# AirQ.net
KiCad netlist of a schematic drawn in Altium Designer
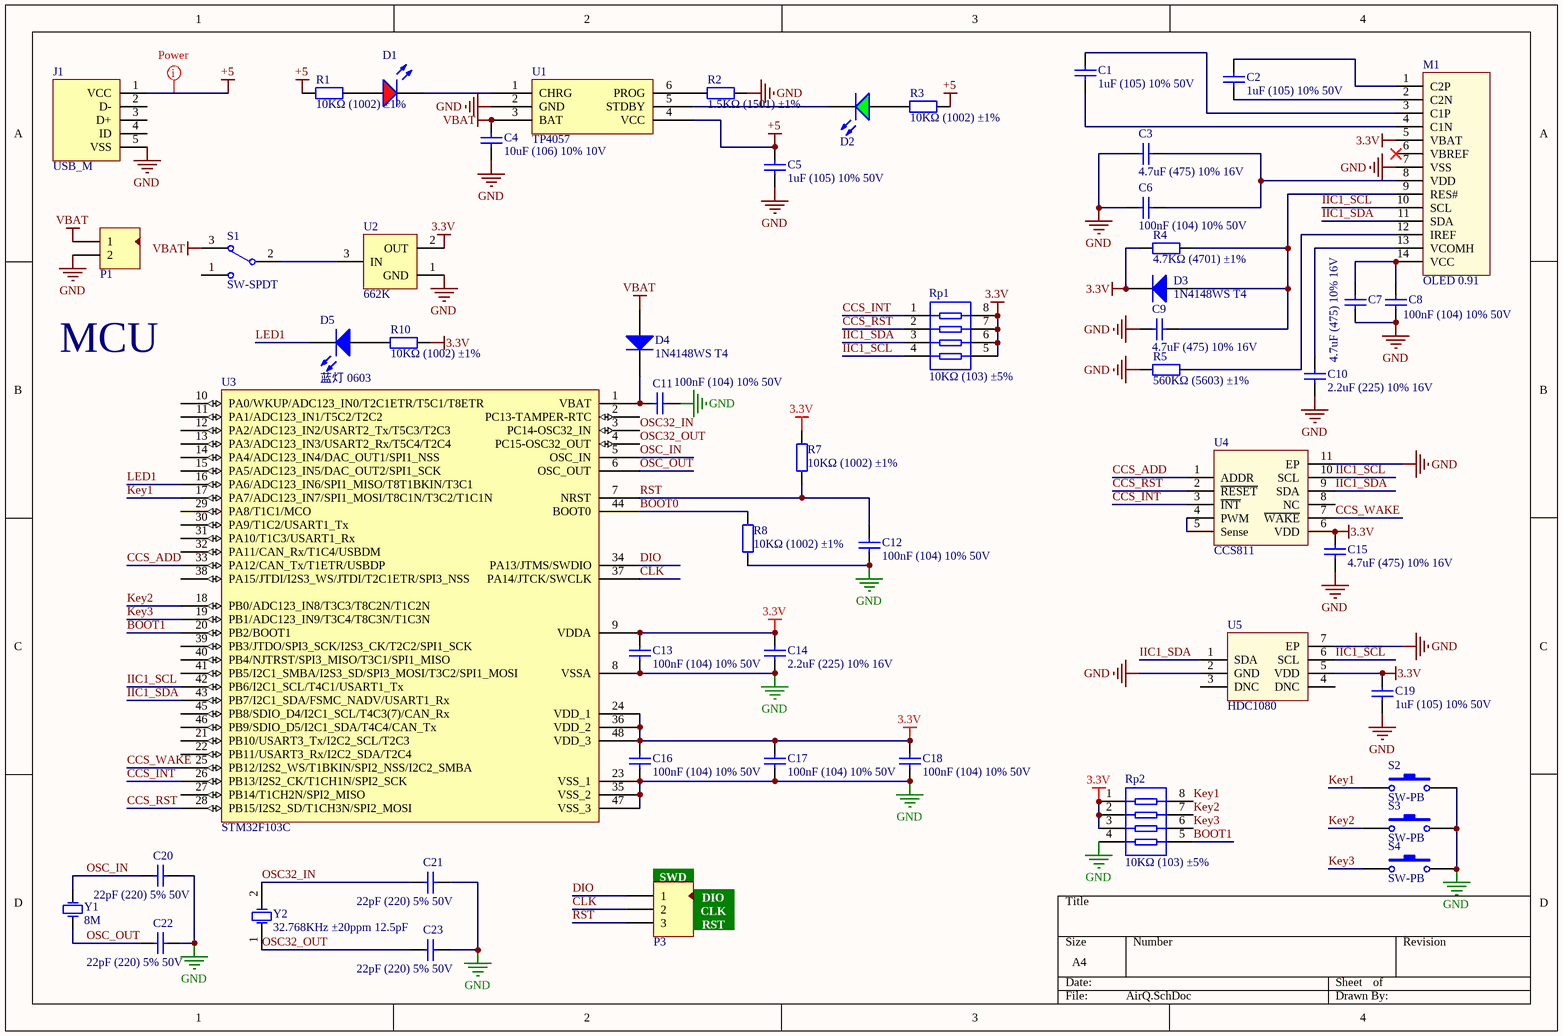
[diagram p0: AirQ.SchDoc]

(export (version "E")
  (design (tool "Eeschema 10.0.6"))
  (components
    (comp (ref "C1")
      (value "1uF (105) 10% 50V")
      (footprint "0603_C")
      (description "贴片电容")
      (libsource (lib "Miscellaneous Devices LC") (part "0603 1uF (105) 10% 50V"))
    )
    (comp (ref "C2")
      (value "1uF (105) 10% 50V")
      (footprint "0603_C")
      (description "贴片电容")
      (libsource (lib "Miscellaneous Devices LC") (part "0603 1uF (105) 10% 50V"))
    )
    (comp (ref "C3")
      (value "4.7uF (475) 10% 16V")
      (footprint "0603_C")
      (description "贴片电容")
      (libsource (lib "Miscellaneous Devices LC") (part "0603 4.7uF (475) 10% 16V"))
    )
    (comp (ref "C4")
      (value "10uF (106) 10% 10V")
      (footprint "0603_C")
      (description "贴片电容")
      (libsource (lib "Miscellaneous Devices LC") (part "0603 10uF (106) 10% 10V"))
    )
    (comp (ref "C5")
      (value "1uF (105) 10% 50V")
      (footprint "0603_C")
      (description "贴片电容")
      (libsource (lib "Miscellaneous Devices LC") (part "0603 1uF (105) 10% 50V"))
    )
    (comp (ref "C6")
      (value "100nF (104) 10% 50V")
      (footprint "0603_C")
      (description "贴片电容")
      (libsource (lib "Miscellaneous Devices LC") (part "0603 100nF (104) 10% 50V"))
    )
    (comp (ref "C7")
      (value "4.7uF (475) 10% 16V")
      (footprint "0603_C")
      (description "贴片电容")
      (libsource (lib "Miscellaneous Devices LC") (part "0603 4.7uF (475) 10% 16V"))
    )
    (comp (ref "C8")
      (value "100nF (104) 10% 50V")
      (footprint "0603_C")
      (description "贴片电容")
      (libsource (lib "Miscellaneous Devices LC") (part "0603 100nF (104) 10% 50V"))
    )
    (comp (ref "C9")
      (value "4.7uF (475) 10% 16V")
      (footprint "0603_C")
      (description "贴片电容")
      (libsource (lib "Miscellaneous Devices LC") (part "0603 4.7uF (475) 10% 16V"))
    )
    (comp (ref "C10")
      (value "2.2uF (225) 10% 16V")
      (footprint "0603_C")
      (description "贴片电容")
      (libsource (lib "Miscellaneous Devices LC") (part "0603 2.2uF (225) 10% 16V"))
    )
    (comp (ref "C11")
      (value "100nF (104) 10% 50V")
      (footprint "0603_C")
      (description "贴片电容")
      (libsource (lib "Miscellaneous Devices LC") (part "0603 100nF (104) 10% 50V"))
    )
    (comp (ref "C12")
      (value "100nF (104) 10% 50V")
      (footprint "0603_C")
      (description "贴片电容")
      (libsource (lib "Miscellaneous Devices LC") (part "0603 100nF (104) 10% 50V"))
    )
    (comp (ref "C13")
      (value "100nF (104) 10% 50V")
      (footprint "0603_C")
      (description "贴片电容")
      (libsource (lib "Miscellaneous Devices LC") (part "0603 100nF (104) 10% 50V"))
    )
    (comp (ref "C14")
      (value "2.2uF (225) 10% 16V")
      (footprint "0603_C")
      (description "贴片电容")
      (libsource (lib "Miscellaneous Devices LC") (part "0603 2.2uF (225) 10% 16V"))
    )
    (comp (ref "C15")
      (value "4.7uF (475) 10% 16V")
      (footprint "0603_C")
      (description "贴片电容")
      (libsource (lib "Miscellaneous Devices LC") (part "0603 4.7uF (475) 10% 16V"))
    )
    (comp (ref "C16")
      (value "100nF (104) 10% 50V")
      (footprint "0603_C")
      (description "贴片电容")
      (libsource (lib "Miscellaneous Devices LC") (part "0603 100nF (104) 10% 50V"))
    )
    (comp (ref "C17")
      (value "100nF (104) 10% 50V")
      (footprint "0603_C")
      (description "贴片电容")
      (libsource (lib "Miscellaneous Devices LC") (part "0603 100nF (104) 10% 50V"))
    )
    (comp (ref "C18")
      (value "100nF (104) 10% 50V")
      (footprint "0603_C")
      (description "贴片电容")
      (libsource (lib "Miscellaneous Devices LC") (part "0603 100nF (104) 10% 50V"))
    )
    (comp (ref "C19")
      (value "1uF (105) 10% 50V")
      (footprint "0603_C")
      (description "贴片电容")
      (libsource (lib "Miscellaneous Devices LC") (part "0603 1uF (105) 10% 50V"))
    )
    (comp (ref "C20")
      (value "22pF (220) 5% 50V")
      (footprint "0603_C")
      (description "贴片电容")
      (libsource (lib "Miscellaneous Devices LC") (part "0603 22pF (220) 5% 50V"))
    )
    (comp (ref "C21")
      (value "22pF (220) 5% 50V")
      (footprint "0603_C")
      (description "贴片电容")
      (libsource (lib "Miscellaneous Devices LC") (part "0603 22pF (220) 5% 50V"))
    )
    (comp (ref "C22")
      (value "22pF (220) 5% 50V")
      (footprint "0603_C")
      (description "贴片电容")
      (libsource (lib "Miscellaneous Devices LC") (part "0603 22pF (220) 5% 50V"))
    )
    (comp (ref "C23")
      (value "22pF (220) 5% 50V")
      (footprint "0603_C")
      (description "贴片电容")
      (libsource (lib "Miscellaneous Devices LC") (part "0603 22pF (220) 5% 50V"))
    )
    (comp (ref "D1")
      (value "红灯 0603")
      (footprint "0603_LED_S1")
      (description "发光二极管")
      (libsource (lib "Miscellaneous Devices LC") (part "0603 红灯"))
    )
    (comp (ref "D2")
      (value "绿灯 0603")
      (footprint "0603_LED_S1")
      (description "发光二极管")
      (libsource (lib "Miscellaneous Devices LC") (part "0603 绿灯"))
    )
    (comp (ref "D3")
      (value "1N4148WS T4")
      (footprint "SOD-323")
      (description "二极管")
      (libsource (lib "Miscellaneous Devices LC") (part "SOD-323 1N4148WS T4"))
    )
    (comp (ref "D4")
      (value "1N4148WS T4")
      (footprint "SOD-323")
      (description "二极管")
      (libsource (lib "Miscellaneous Devices LC") (part "SOD-323 1N4148WS T4"))
    )
    (comp (ref "D5")
      (value "蓝灯 0603")
      (footprint "0603_LED_S1")
      (description "发光二极管")
      (libsource (lib "Miscellaneous Devices LC") (part "0603 蓝灯"))
    )
    (comp (ref "J1")
      (value "USB_M")
      (footprint "USB-MICRO-A01SB141B1-261")
      (description "Micro/Mini USB")
      (libsource (lib "interface") (part "USB_M"))
    )
    (comp (ref "M1")
      (value "OLED 0.91")
      (footprint "OLED 0.91 BOTTOM")
      (description "0.91寸OLED裸屏")
      (libsource (lib "function module") (part "OLED-0.91"))
    )
    (comp (ref "P1")
      (value "Header 2")
      (footprint "HDR2X1-2.54")
      (description "接插件")
      (fields (field (name "PUBLISHER") "Altium Limited"))
      (libsource (lib "interface") (part "Header 2"))
    )
    (comp (ref "P3")
      (value "Header 3")
      (footprint "HDR3X1-2.54")
      (description "接插件")
      (fields (field (name "PUBLISHER") "Altium Limited"))
      (libsource (lib "interface") (part "Header 3"))
    )
    (comp (ref "R1")
      (value "10KΩ (1002) ±1%")
      (footprint "0603_R")
      (description "贴片电阻")
      (libsource (lib "Miscellaneous Devices LC") (part "0603 10KΩ (1002) 1%"))
    )
    (comp (ref "R2")
      (value "1.5KΩ (1501) ±1%")
      (footprint "0603_R")
      (description "贴片电阻")
      (libsource (lib "Miscellaneous Devices LC") (part "0603 1.5KΩ (1501) 1%"))
    )
    (comp (ref "R3")
      (value "10KΩ (1002) ±1%")
      (footprint "0603_R")
      (description "贴片电阻")
      (libsource (lib "") (part "0603 10KΩ (1002) 1%_1"))
    )
    (comp (ref "R4")
      (value "4.7KΩ (4701) ±1%")
      (footprint "0603_R")
      (description "贴片电阻")
      (libsource (lib "Miscellaneous Devices LC") (part "0603 4.7KΩ (4701) 1%"))
    )
    (comp (ref "R5")
      (value "560KΩ (5603) ±1%")
      (footprint "0603_R")
      (description "贴片电阻")
      (libsource (lib "Miscellaneous Devices LC") (part "0603 560KΩ (5603) 1%"))
    )
    (comp (ref "R7")
      (value "10KΩ (1002) ±1%")
      (footprint "0603_R")
      (description "贴片电阻")
      (libsource (lib "") (part "0603 10KΩ (1002) 1%_2"))
    )
    (comp (ref "R8")
      (value "10KΩ (1002) ±1%")
      (footprint "0603_R")
      (description "贴片电阻")
      (libsource (lib "") (part "0603 10KΩ (1002) 1%_2"))
    )
    (comp (ref "R10")
      (value "10KΩ (1002) ±1%")
      (footprint "0603_R")
      (description "贴片电阻")
      (libsource (lib "") (part "0603 10KΩ (1002) 1%_1"))
    )
    (comp (ref "Rp1")
      (value "10KΩ (103) ±5%")
      (footprint "0603_Rx4")
      (description "贴片排阻")
      (libsource (lib "Miscellaneous Devices LC") (part "0603*4  10KΩ (103) 5%"))
    )
    (comp (ref "Rp2")
      (value "10KΩ (103) ±5%")
      (footprint "0603_Rx4")
      (description "贴片排阻")
      (libsource (lib "Miscellaneous Devices LC") (part "0603*4  10KΩ (103) 5%"))
    )
    (comp (ref "S1")
      (value "SW-SPDT")
      (footprint "SWITCH_SMT1")
      (description "开关")
      (fields (field (name "PUBLISHER") "Altium Limited"))
      (libsource (lib "Fszhang") (part "SW-SPDT"))
    )
    (comp (ref "S2")
      (value "SW-PB")
      (footprint "SW_PB2_A1")
      (description "微动开关")
      (fields (field (name "PUBLISHER") "Altium Limited"))
      (libsource (lib "fszhang") (part "SW-PB"))
    )
    (comp (ref "S3")
      (value "SW-PB")
      (footprint "SW_PB2_A1")
      (description "微动开关")
      (fields (field (name "PUBLISHER") "Altium Limited"))
      (libsource (lib "fszhang") (part "SW-PB"))
    )
    (comp (ref "S4")
      (value "SW-PB")
      (footprint "SW_PB2_A1")
      (description "微动开关")
      (fields (field (name "PUBLISHER") "Altium Limited"))
      (libsource (lib "fszhang") (part "SW-PB"))
    )
    (comp (ref "U1")
      (value "TP4057")
      (footprint "SOT-23-6")
      (description "电池电源管理")
      (libsource (lib "Miscellaneous Devices LC") (part "TP4057_[C12044]"))
    )
    (comp (ref "U2")
      (value "662K")
      (footprint "SOT23-3")
      (description "3.3V稳压三极管 662K")
      (libsource (lib "Fszhang") (part "XC6206P332MR"))
    )
    (comp (ref "U3")
      (value "STM32F103C")
      (footprint "LQFP-48")
      (description "STM32单片机48引脚")
      (libsource (lib "Fszhang") (part "STM32F103C"))
    )
    (comp (ref "U4")
      (value "CCS811")
      (footprint "CCS811")
      (description "空气质量检测")
      (libsource (lib "Sensor") (part "CCS811"))
    )
    (comp (ref "U5")
      (value "HDC1080")
      (footprint "HDC1080")
      (description "温湿度传感器")
      (libsource (lib "Sensor") (part "HDC1080"))
    )
    (comp (ref "Y1")
      (value "8M")
      (footprint "5032 - 2Pin")
      (description "晶振")
      (fields (field (name "Comment") "XTAL") (field (name "PUBLISHER") "Altium Limited"))
      (libsource (lib "fszhang") (part "XTAL"))
    )
    (comp (ref "Y2")
      (value "32.768KHz ±20ppm 12.5pF")
      (footprint "SMD-3215_2P FC - 135")
      (description "贴片晶振")
      (libsource (lib "Miscellaneous Devices LC") (part "SMD-3215_2P 32.768KHz 20ppm 12.5pF"))
    )
  )
  (nets
    (net (code "1") (name "+5") (class "Default")
      (node (ref "C5") (pin "2") (pinfunction "2_2") (pintype "passive"))
      (node (ref "J1") (pin "1") (pinfunction "VCC_1") (pintype "power_in"))
      (node (ref "R1") (pin "1") (pinfunction "1_1") (pintype "passive"))
      (node (ref "R3") (pin "1") (pinfunction "1_1") (pintype "passive"))
      (node (ref "U1") (pin "4") (pinfunction "VCC_4") (pintype "passive"))
    )
    (net (code "2") (name "/BOOT0") (class "Default")
      (node (ref "R8") (pin "2") (pinfunction "2_2") (pintype "passive"))
      (node (ref "U3") (pin "44") (pinfunction "BOOT0_44") (pintype "passive"))
    )
    (net (code "3") (name "/BOOT1") (class "Default")
      (node (ref "Rp2") (pin "5") (pinfunction "5_5") (pintype "passive"))
      (node (ref "U3") (pin "20") (pinfunction "PB2/BOOT1_20") (pintype "bidirectional"))
    )
    (net (code "4") (name "/CCS_ADD") (class "Default")
      (node (ref "U3") (pin "33") (pinfunction "PA12/CAN_Tx/T1ETR/USBDP_33") (pintype "bidirectional"))
      (node (ref "U4") (pin "1") (pinfunction "ADDR_1") (pintype "passive"))
    )
    (net (code "5") (name "/CCS_INT") (class "Default")
      (node (ref "Rp1") (pin "1") (pinfunction "1_1") (pintype "passive"))
      (node (ref "U3") (pin "26") (pinfunction "PB13/I2S2_CK/T1CH1N/SPI2_SCK_26") (pintype "bidirectional"))
      (node (ref "U4") (pin "3") (pinfunction "~{INT}_3") (pintype "passive"))
    )
    (net (code "6") (name "/CCS_RST") (class "Default")
      (node (ref "Rp1") (pin "2") (pinfunction "2_2") (pintype "passive"))
      (node (ref "U3") (pin "28") (pinfunction "PB15/I2S2_SD/T1CH3N/SPI2_MOSI_28") (pintype "bidirectional"))
      (node (ref "U4") (pin "2") (pinfunction "~{RESET}_2") (pintype "passive"))
    )
    (net (code "7") (name "/CCS_WAKE") (class "Default")
      (node (ref "U3") (pin "25") (pinfunction "PB12/I2S2_WS/T1BKIN/SPI2_NSS/I2C2_SMBA_25") (pintype "bidirectional"))
      (node (ref "U4") (pin "7") (pinfunction "~{WAKE}_7") (pintype "passive"))
    )
    (net (code "8") (name "/CLK") (class "Default")
      (node (ref "P3") (pin "2") (pinfunction "2_2") (pintype "passive"))
      (node (ref "U3") (pin "37") (pinfunction "PA14/JTCK/SWCLK_37") (pintype "passive"))
    )
    (net (code "9") (name "/DIO") (class "Default")
      (node (ref "P3") (pin "1") (pinfunction "1_1") (pintype "passive"))
      (node (ref "U3") (pin "34") (pinfunction "PA13/JTMS/SWDIO_34") (pintype "passive"))
    )
    (net (code "10") (name "/IIC1_SCL") (class "Default")
      (node (ref "M1") (pin "10") (pinfunction "SCL_10") (pintype "passive"))
      (node (ref "Rp1") (pin "4") (pinfunction "4_4") (pintype "passive"))
      (node (ref "U3") (pin "42") (pinfunction "PB6/I2C1_SCL/T4C1/USART1_Tx_42") (pintype "bidirectional"))
      (node (ref "U4") (pin "10") (pinfunction "SCL_10") (pintype "passive"))
      (node (ref "U5") (pin "6") (pinfunction "SCL_6") (pintype "passive"))
    )
    (net (code "11") (name "/IIC1_SDA") (class "Default")
      (node (ref "M1") (pin "11") (pinfunction "SDA_11") (pintype "passive"))
      (node (ref "Rp1") (pin "3") (pinfunction "3_3") (pintype "passive"))
      (node (ref "U3") (pin "43") (pinfunction "PB7/I2C1_SDA/FSMC_NADV/USART1_Rx_43") (pintype "bidirectional"))
      (node (ref "U4") (pin "9") (pinfunction "SDA_9") (pintype "passive"))
      (node (ref "U5") (pin "1") (pinfunction "SDA_1") (pintype "passive"))
    )
    (net (code "12") (name "/Key1") (class "Default")
      (node (ref "Rp2") (pin "8") (pinfunction "8_8") (pintype "passive"))
      (node (ref "S2") (pin "1") (pinfunction "1_1") (pintype "passive"))
      (node (ref "U3") (pin "17") (pinfunction "PA7/ADC123_IN7/SPI1_MOSI/T8C1N/T3C2/T1C1N_17") (pintype "bidirectional"))
    )
    (net (code "13") (name "/Key2") (class "Default")
      (node (ref "Rp2") (pin "7") (pinfunction "7_7") (pintype "passive"))
      (node (ref "S3") (pin "1") (pinfunction "1_1") (pintype "passive"))
      (node (ref "U3") (pin "18") (pinfunction "PB0/ADC123_IN8/T3C3/T8C2N/T1C2N_18") (pintype "bidirectional"))
    )
    (net (code "14") (name "/Key3") (class "Default")
      (node (ref "Rp2") (pin "6") (pinfunction "6_6") (pintype "passive"))
      (node (ref "S4") (pin "1") (pinfunction "1_1") (pintype "passive"))
      (node (ref "U3") (pin "19") (pinfunction "PB1/ADC123_IN9/T3C4/T8C3N/T1C3N_19") (pintype "bidirectional"))
    )
    (net (code "15") (name "/LED1") (class "Default")
      (node (ref "D5") (pin "K") (pinfunction "K_K") (pintype "passive"))
      (node (ref "U3") (pin "16") (pinfunction "PA6/ADC123_IN6/SPI1_MISO/T8T1BKIN/T3C1_16") (pintype "bidirectional"))
    )
    (net (code "16") (name "/OSC32_IN") (class "Default")
      (node (ref "C21") (pin "1") (pinfunction "1_1") (pintype "passive"))
      (node (ref "U3") (pin "3") (pinfunction "PC14-OSC32_IN_3") (pintype "bidirectional"))
      (node (ref "Y2") (pin "2") (pinfunction "OSC2_2") (pintype "passive"))
    )
    (net (code "17") (name "/OSC32_OUT") (class "Default")
      (node (ref "C23") (pin "1") (pinfunction "1_1") (pintype "passive"))
      (node (ref "U3") (pin "4") (pinfunction "PC15-OSC32_OUT_4") (pintype "bidirectional"))
      (node (ref "Y2") (pin "1") (pinfunction "OSC1_1") (pintype "passive"))
    )
    (net (code "18") (name "/OSC_IN") (class "Default")
      (node (ref "C20") (pin "1") (pinfunction "1_1") (pintype "passive"))
      (node (ref "U3") (pin "5") (pinfunction "OSC_IN_5") (pintype "passive"))
      (node (ref "Y1") (pin "2") (pinfunction "OSC2_2") (pintype "passive"))
    )
    (net (code "19") (name "/OSC_OUT") (class "Default")
      (node (ref "C22") (pin "1") (pinfunction "1_1") (pintype "passive"))
      (node (ref "U3") (pin "6") (pinfunction "OSC_OUT_6") (pintype "passive"))
      (node (ref "Y1") (pin "1") (pinfunction "OSC1_1") (pintype "passive"))
    )
    (net (code "20") (name "/RST") (class "Default")
      (node (ref "C12") (pin "2") (pinfunction "2_2") (pintype "passive"))
      (node (ref "P3") (pin "3") (pinfunction "3_3") (pintype "passive"))
      (node (ref "R7") (pin "1") (pinfunction "1_1") (pintype "passive"))
      (node (ref "U3") (pin "7") (pinfunction "NRST_7") (pintype "passive"))
    )
    (net (code "21") (name "3.3V") (class "Default")
      (node (ref "C13") (pin "2") (pinfunction "2_2") (pintype "passive"))
      (node (ref "C14") (pin "2") (pinfunction "2_2") (pintype "passive"))
      (node (ref "C15") (pin "2") (pinfunction "2_2") (pintype "passive"))
      (node (ref "C16") (pin "2") (pinfunction "2_2") (pintype "passive"))
      (node (ref "C17") (pin "2") (pinfunction "2_2") (pintype "passive"))
      (node (ref "C18") (pin "2") (pinfunction "2_2") (pintype "passive"))
      (node (ref "C19") (pin "2") (pinfunction "2_2") (pintype "passive"))
      (node (ref "D3") (pin "2") (pinfunction "K_2") (pintype "passive"))
      (node (ref "M1") (pin "5") (pinfunction "VBAT_5") (pintype "passive"))
      (node (ref "R10") (pin "1") (pinfunction "1_1") (pintype "passive"))
      (node (ref "R4") (pin "2") (pinfunction "2_2") (pintype "passive"))
      (node (ref "R7") (pin "2") (pinfunction "2_2") (pintype "passive"))
      (node (ref "Rp1") (pin "5") (pinfunction "5_5") (pintype "passive"))
      (node (ref "Rp1") (pin "6") (pinfunction "6_6") (pintype "passive"))
      (node (ref "Rp1") (pin "7") (pinfunction "7_7") (pintype "passive"))
      (node (ref "Rp1") (pin "8") (pinfunction "8_8") (pintype "passive"))
      (node (ref "Rp2") (pin "1") (pinfunction "1_1") (pintype "passive"))
      (node (ref "Rp2") (pin "2") (pinfunction "2_2") (pintype "passive"))
      (node (ref "Rp2") (pin "3") (pinfunction "3_3") (pintype "passive"))
      (node (ref "U2") (pin "2") (pinfunction "OUT_2") (pintype "passive"))
      (node (ref "U3") (pin "24") (pinfunction "VDD_1_24") (pintype "passive"))
      (node (ref "U3") (pin "36") (pinfunction "VDD_2_36") (pintype "passive"))
      (node (ref "U3") (pin "48") (pinfunction "VDD_3_48") (pintype "passive"))
      (node (ref "U3") (pin "9") (pinfunction "VDDA_9") (pintype "passive"))
      (node (ref "U4") (pin "6") (pinfunction "VDD_6") (pintype "passive"))
      (node (ref "U5") (pin "5") (pinfunction "VDD_5") (pintype "passive"))
    )
    (net (code "22") (name "GND") (class "Default")
      (node (ref "C10") (pin "1") (pinfunction "1_1") (pintype "passive"))
      (node (ref "C11") (pin "1") (pinfunction "1_1") (pintype "passive"))
      (node (ref "C12") (pin "1") (pinfunction "1_1") (pintype "passive"))
      (node (ref "C13") (pin "1") (pinfunction "1_1") (pintype "passive"))
      (node (ref "C14") (pin "1") (pinfunction "1_1") (pintype "passive"))
      (node (ref "C15") (pin "1") (pinfunction "1_1") (pintype "passive"))
      (node (ref "C16") (pin "1") (pinfunction "1_1") (pintype "passive"))
      (node (ref "C17") (pin "1") (pinfunction "1_1") (pintype "passive"))
      (node (ref "C18") (pin "1") (pinfunction "1_1") (pintype "passive"))
      (node (ref "C19") (pin "1") (pinfunction "1_1") (pintype "passive"))
      (node (ref "C20") (pin "2") (pinfunction "2_2") (pintype "passive"))
      (node (ref "C21") (pin "2") (pinfunction "2_2") (pintype "passive"))
      (node (ref "C22") (pin "2") (pinfunction "2_2") (pintype "passive"))
      (node (ref "C23") (pin "2") (pinfunction "2_2") (pintype "passive"))
      (node (ref "C3") (pin "2") (pinfunction "2_2") (pintype "passive"))
      (node (ref "C4") (pin "1") (pinfunction "1_1") (pintype "passive"))
      (node (ref "C5") (pin "1") (pinfunction "1_1") (pintype "passive"))
      (node (ref "C6") (pin "2") (pinfunction "2_2") (pintype "passive"))
      (node (ref "C7") (pin "2") (pinfunction "2_2") (pintype "passive"))
      (node (ref "C8") (pin "2") (pinfunction "2_2") (pintype "passive"))
      (node (ref "C9") (pin "1") (pinfunction "1_1") (pintype "passive"))
      (node (ref "J1") (pin "5") (pinfunction "VSS_5") (pintype "power_in"))
      (node (ref "M1") (pin "7") (pinfunction "VSS_7") (pintype "passive"))
      (node (ref "P1") (pin "2") (pinfunction "2_2") (pintype "passive"))
      (node (ref "R2") (pin "2") (pinfunction "2_2") (pintype "passive"))
      (node (ref "R5") (pin "2") (pinfunction "2_2") (pintype "passive"))
      (node (ref "R8") (pin "1") (pinfunction "1_1") (pintype "passive"))
      (node (ref "Rp2") (pin "4") (pinfunction "4_4") (pintype "passive"))
      (node (ref "S2") (pin "2") (pinfunction "2_2") (pintype "passive"))
      (node (ref "S3") (pin "2") (pinfunction "2_2") (pintype "passive"))
      (node (ref "S4") (pin "2") (pinfunction "2_2") (pintype "passive"))
      (node (ref "U1") (pin "2") (pinfunction "GND_2") (pintype "passive"))
      (node (ref "U2") (pin "1") (pinfunction "GND_1") (pintype "passive"))
      (node (ref "U3") (pin "23") (pinfunction "VSS_1_23") (pintype "passive"))
      (node (ref "U3") (pin "35") (pinfunction "VSS_2_35") (pintype "passive"))
      (node (ref "U3") (pin "47") (pinfunction "VSS_3_47") (pintype "passive"))
      (node (ref "U3") (pin "8") (pinfunction "VSSA_8") (pintype "passive"))
      (node (ref "U4") (pin "11") (pinfunction "EP_11") (pintype "passive"))
      (node (ref "U5") (pin "2") (pinfunction "GND_2") (pintype "passive"))
      (node (ref "U5") (pin "7") (pinfunction "EP_7") (pintype "passive"))
    )
    (net (code "23") (name "Net-(D1-PadA)") (class "Default")
      (node (ref "D1") (pin "A") (pinfunction "A_A") (pintype "passive"))
      (node (ref "R1") (pin "2") (pinfunction "2_2") (pintype "passive"))
    )
    (net (code "24") (name "Net-(D2-PadA)") (class "Default")
      (node (ref "D2") (pin "A") (pinfunction "A_A") (pintype "passive"))
      (node (ref "R3") (pin "2") (pinfunction "2_2") (pintype "passive"))
    )
    (net (code "25") (name "Net-(D3-A)") (class "Default")
      (node (ref "C9") (pin "2") (pinfunction "2_2") (pintype "passive"))
      (node (ref "D3") (pin "1") (pinfunction "A_1") (pintype "passive"))
      (node (ref "M1") (pin "9") (pinfunction "RES#_9") (pintype "passive"))
      (node (ref "R4") (pin "1") (pinfunction "1_1") (pintype "passive"))
    )
    (net (code "26") (name "Net-(D4-K)") (class "Default")
      (node (ref "C11") (pin "2") (pinfunction "2_2") (pintype "passive"))
      (node (ref "D4") (pin "2") (pinfunction "K_2") (pintype "passive"))
      (node (ref "U3") (pin "1") (pinfunction "VBAT_1") (pintype "passive"))
    )
    (net (code "27") (name "Net-(D5-PadA)") (class "Default")
      (node (ref "D5") (pin "A") (pinfunction "A_A") (pintype "passive"))
      (node (ref "R10") (pin "2") (pinfunction "2_2") (pintype "passive"))
    )
    (net (code "28") (name "Net-(M1-C1N)") (class "Default")
      (node (ref "C1") (pin "1") (pinfunction "1_1") (pintype "passive"))
      (node (ref "M1") (pin "4") (pinfunction "C1N_4") (pintype "passive"))
    )
    (net (code "29") (name "Net-(M1-C1P)") (class "Default")
      (node (ref "C1") (pin "2") (pinfunction "2_2") (pintype "passive"))
      (node (ref "M1") (pin "3") (pinfunction "C1P_3") (pintype "passive"))
    )
    (net (code "30") (name "Net-(M1-C2N)") (class "Default")
      (node (ref "C2") (pin "1") (pinfunction "1_1") (pintype "passive"))
      (node (ref "M1") (pin "2") (pinfunction "C2N_2") (pintype "passive"))
    )
    (net (code "31") (name "Net-(M1-C2P)") (class "Default")
      (node (ref "C2") (pin "2") (pinfunction "2_2") (pintype "passive"))
      (node (ref "M1") (pin "1") (pinfunction "C2P_1") (pintype "passive"))
    )
    (net (code "32") (name "Net-(M1-IREF)") (class "Default")
      (node (ref "M1") (pin "12") (pinfunction "IREF_12") (pintype "passive"))
      (node (ref "R5") (pin "1") (pinfunction "1_1") (pintype "passive"))
    )
    (net (code "33") (name "Net-(M1-VCC)") (class "Default")
      (node (ref "C7") (pin "1") (pinfunction "1_1") (pintype "passive"))
      (node (ref "C8") (pin "1") (pinfunction "1_1") (pintype "passive"))
      (node (ref "M1") (pin "14") (pinfunction "VCC_14") (pintype "passive"))
    )
    (net (code "34") (name "Net-(M1-VCOMH)") (class "Default")
      (node (ref "C10") (pin "2") (pinfunction "2_2") (pintype "passive"))
      (node (ref "M1") (pin "13") (pinfunction "VCOMH_13") (pintype "passive"))
    )
    (net (code "35") (name "Net-(M1-VDD)") (class "Default")
      (node (ref "C3") (pin "1") (pinfunction "1_1") (pintype "passive"))
      (node (ref "C6") (pin "1") (pinfunction "1_1") (pintype "passive"))
      (node (ref "M1") (pin "8") (pinfunction "VDD_8") (pintype "passive"))
    )
    (net (code "36") (name "Net-(U1-CHRG)") (class "Default")
      (node (ref "D1") (pin "K") (pinfunction "K_K") (pintype "passive"))
      (node (ref "U1") (pin "1") (pinfunction "CHRG_1") (pintype "passive"))
    )
    (net (code "37") (name "Net-(U1-PROG)") (class "Default")
      (node (ref "R2") (pin "1") (pinfunction "1_1") (pintype "passive"))
      (node (ref "U1") (pin "6") (pinfunction "PROG_6") (pintype "passive"))
    )
    (net (code "38") (name "Net-(U1-STDBY)") (class "Default")
      (node (ref "D2") (pin "K") (pinfunction "K_K") (pintype "passive"))
      (node (ref "U1") (pin "5") (pinfunction "STDBY_5") (pintype "passive"))
    )
    (net (code "39") (name "Net-(U2-IN)") (class "Default")
      (node (ref "S1") (pin "2") (pinfunction "2_2") (pintype "passive"))
      (node (ref "U2") (pin "3") (pinfunction "IN_3") (pintype "passive"))
    )
    (net (code "40") (name "Net-(U4-PWM)") (class "Default")
      (node (ref "U4") (pin "4") (pinfunction "PWM_4") (pintype "passive"))
      (node (ref "U4") (pin "5") (pinfunction "Sense_5") (pintype "passive"))
    )
    (net (code "41") (name "VBAT") (class "Default")
      (node (ref "C4") (pin "2") (pinfunction "2_2") (pintype "passive"))
      (node (ref "D4") (pin "1") (pinfunction "A_1") (pintype "passive"))
      (node (ref "P1") (pin "1") (pinfunction "1_1") (pintype "passive"))
      (node (ref "S1") (pin "3") (pinfunction "3_3") (pintype "passive"))
      (node (ref "U1") (pin "3") (pinfunction "BAT_3") (pintype "passive"))
    )
    (net (code "42") (name "unconnected-(J1-D+-Pad3)") (class "Default")
      (node (ref "J1") (pin "3") (pinfunction "D+_3") (pintype "passive"))
    )
    (net (code "43") (name "unconnected-(J1-D--Pad2)") (class "Default")
      (node (ref "J1") (pin "2") (pinfunction "D-_2") (pintype "passive"))
    )
    (net (code "44") (name "unconnected-(J1-ID-Pad4)") (class "Default")
      (node (ref "J1") (pin "4") (pinfunction "ID_4") (pintype "passive"))
    )
    (net (code "45") (name "unconnected-(M1-VBREF-Pad6)") (class "Default")
      (node (ref "M1") (pin "6") (pinfunction "VBREF_6") (pintype "passive+no_connect"))
    )
    (net (code "46") (name "unconnected-(S1-Pad1)") (class "Default")
      (node (ref "S1") (pin "1") (pinfunction "1_1") (pintype "passive"))
    )
    (net (code "47") (name "unconnected-(U3-PA0{slash}WKUP{slash}ADC123_IN0{slash}T2C1ETR{slash}T5C1{slash}T8ETR-Pad10)") (class "Default")
      (node (ref "U3") (pin "10") (pinfunction "PA0/WKUP/ADC123_IN0/T2C1ETR/T5C1/T8ETR_10") (pintype "bidirectional"))
    )
    (net (code "48") (name "unconnected-(U3-PA1{slash}ADC123_IN1{slash}T5C2{slash}T2C2-Pad11)") (class "Default")
      (node (ref "U3") (pin "11") (pinfunction "PA1/ADC123_IN1/T5C2/T2C2_11") (pintype "bidirectional"))
    )
    (net (code "49") (name "unconnected-(U3-PA2{slash}ADC123_IN2{slash}USART2_Tx{slash}T5C3{slash}T2C3-Pad12)") (class "Default")
      (node (ref "U3") (pin "12") (pinfunction "PA2/ADC123_IN2/USART2_Tx/T5C3/T2C3_12") (pintype "bidirectional"))
    )
    (net (code "50") (name "unconnected-(U3-PA3{slash}ADC123_IN3{slash}USART2_Rx{slash}T5C4{slash}T2C4-Pad13)") (class "Default")
      (node (ref "U3") (pin "13") (pinfunction "PA3/ADC123_IN3/USART2_Rx/T5C4/T2C4_13") (pintype "bidirectional"))
    )
    (net (code "51") (name "unconnected-(U3-PA4{slash}ADC123_IN4{slash}DAC_OUT1{slash}SPI1_NSS-Pad14)") (class "Default")
      (node (ref "U3") (pin "14") (pinfunction "PA4/ADC123_IN4/DAC_OUT1/SPI1_NSS_14") (pintype "bidirectional"))
    )
    (net (code "52") (name "unconnected-(U3-PA5{slash}ADC123_IN5{slash}DAC_OUT2{slash}SPI1_SCK-Pad15)") (class "Default")
      (node (ref "U3") (pin "15") (pinfunction "PA5/ADC123_IN5/DAC_OUT2/SPI1_SCK_15") (pintype "bidirectional"))
    )
    (net (code "53") (name "unconnected-(U3-PA8{slash}T1C1{slash}MCO-Pad29)") (class "Default")
      (node (ref "U3") (pin "29") (pinfunction "PA8/T1C1/MCO_29") (pintype "bidirectional"))
    )
    (net (code "54") (name "unconnected-(U3-PA9{slash}T1C2{slash}USART1_Tx-Pad30)") (class "Default")
      (node (ref "U3") (pin "30") (pinfunction "PA9/T1C2/USART1_Tx_30") (pintype "bidirectional"))
    )
    (net (code "55") (name "unconnected-(U3-PA10{slash}T1C3{slash}USART1_Rx-Pad31)") (class "Default")
      (node (ref "U3") (pin "31") (pinfunction "PA10/T1C3/USART1_Rx_31") (pintype "bidirectional"))
    )
    (net (code "56") (name "unconnected-(U3-PA11{slash}CAN_Rx{slash}T1C4{slash}USBDM-Pad32)") (class "Default")
      (node (ref "U3") (pin "32") (pinfunction "PA11/CAN_Rx/T1C4/USBDM_32") (pintype "bidirectional"))
    )
    (net (code "57") (name "unconnected-(U3-PA15{slash}JTDI{slash}I2S3_WS{slash}JTDI{slash}T2C1ETR{slash}SPI3_NSS-Pad38)") (class "Default")
      (node (ref "U3") (pin "38") (pinfunction "PA15/JTDI/I2S3_WS/JTDI/T2C1ETR/SPI3_NSS_38") (pintype "bidirectional"))
    )
    (net (code "58") (name "unconnected-(U3-PB3{slash}JTDO{slash}SPI3_SCK{slash}I2S3_CK{slash}T2C2{slash}SPI1_SCK-Pad39)") (class "Default")
      (node (ref "U3") (pin "39") (pinfunction "PB3/JTDO/SPI3_SCK/I2S3_CK/T2C2/SPI1_SCK_39") (pintype "bidirectional"))
    )
    (net (code "59") (name "unconnected-(U3-PB4{slash}NJTRST{slash}SPI3_MISO{slash}T3C1{slash}SPI1_MISO-Pad40)") (class "Default")
      (node (ref "U3") (pin "40") (pinfunction "PB4/NJTRST/SPI3_MISO/T3C1/SPI1_MISO_40") (pintype "bidirectional"))
    )
    (net (code "60") (name "unconnected-(U3-PB5{slash}I2C1_SMBA{slash}I2S3_SD{slash}SPI3_MOSI{slash}T3C2{slash}SPI1_MOSI-Pad41)") (class "Default")
      (node (ref "U3") (pin "41") (pinfunction "PB5/I2C1_SMBA/I2S3_SD/SPI3_MOSI/T3C2/SPI1_MOSI_41") (pintype "bidirectional"))
    )
    (net (code "61") (name "unconnected-(U3-PB8{slash}SDIO_D4{slash}I2C1_SCL{slash}T4C3(7){slash}CAN_Rx-Pad45)") (class "Default")
      (node (ref "U3") (pin "45") (pinfunction "PB8/SDIO_D4/I2C1_SCL/T4C3(7)/CAN_Rx_45") (pintype "bidirectional"))
    )
    (net (code "62") (name "unconnected-(U3-PB9{slash}SDIO_D5{slash}I2C1_SDA{slash}T4C4{slash}CAN_Tx-Pad46)") (class "Default")
      (node (ref "U3") (pin "46") (pinfunction "PB9/SDIO_D5/I2C1_SDA/T4C4/CAN_Tx_46") (pintype "bidirectional"))
    )
    (net (code "63") (name "unconnected-(U3-PB10{slash}USART3_Tx{slash}I2C2_SCL{slash}T2C3-Pad21)") (class "Default")
      (node (ref "U3") (pin "21") (pinfunction "PB10/USART3_Tx/I2C2_SCL/T2C3_21") (pintype "bidirectional"))
    )
    (net (code "64") (name "unconnected-(U3-PB11{slash}USART3_Rx{slash}I2C2_SDA{slash}T2C4-Pad22)") (class "Default")
      (node (ref "U3") (pin "22") (pinfunction "PB11/USART3_Rx/I2C2_SDA/T2C4_22") (pintype "bidirectional"))
    )
    (net (code "65") (name "unconnected-(U3-PB14{slash}T1CH2N{slash}SPI2_MISO-Pad27)") (class "Default")
      (node (ref "U3") (pin "27") (pinfunction "PB14/T1CH2N/SPI2_MISO_27") (pintype "bidirectional"))
    )
    (net (code "66") (name "unconnected-(U3-PC13-TAMPER-RTC-Pad2)") (class "Default")
      (node (ref "U3") (pin "2") (pinfunction "PC13-TAMPER-RTC_2") (pintype "bidirectional"))
    )
    (net (code "67") (name "unconnected-(U4-NC-Pad8)") (class "Default")
      (node (ref "U4") (pin "8") (pinfunction "NC_8") (pintype "passive"))
    )
    (net (code "68") (name "unconnected-(U5-DNC-Pad3)") (class "Default")
      (node (ref "U5") (pin "3") (pinfunction "DNC_3") (pintype "passive"))
    )
    (net (code "69") (name "unconnected-(U5-DNC-Pad4)") (class "Default")
      (node (ref "U5") (pin "4") (pinfunction "DNC_4") (pintype "passive"))
    )
  )
)
